# LVDS_Driver.net
KiCad netlist of a schematic drawn in Altium Designer
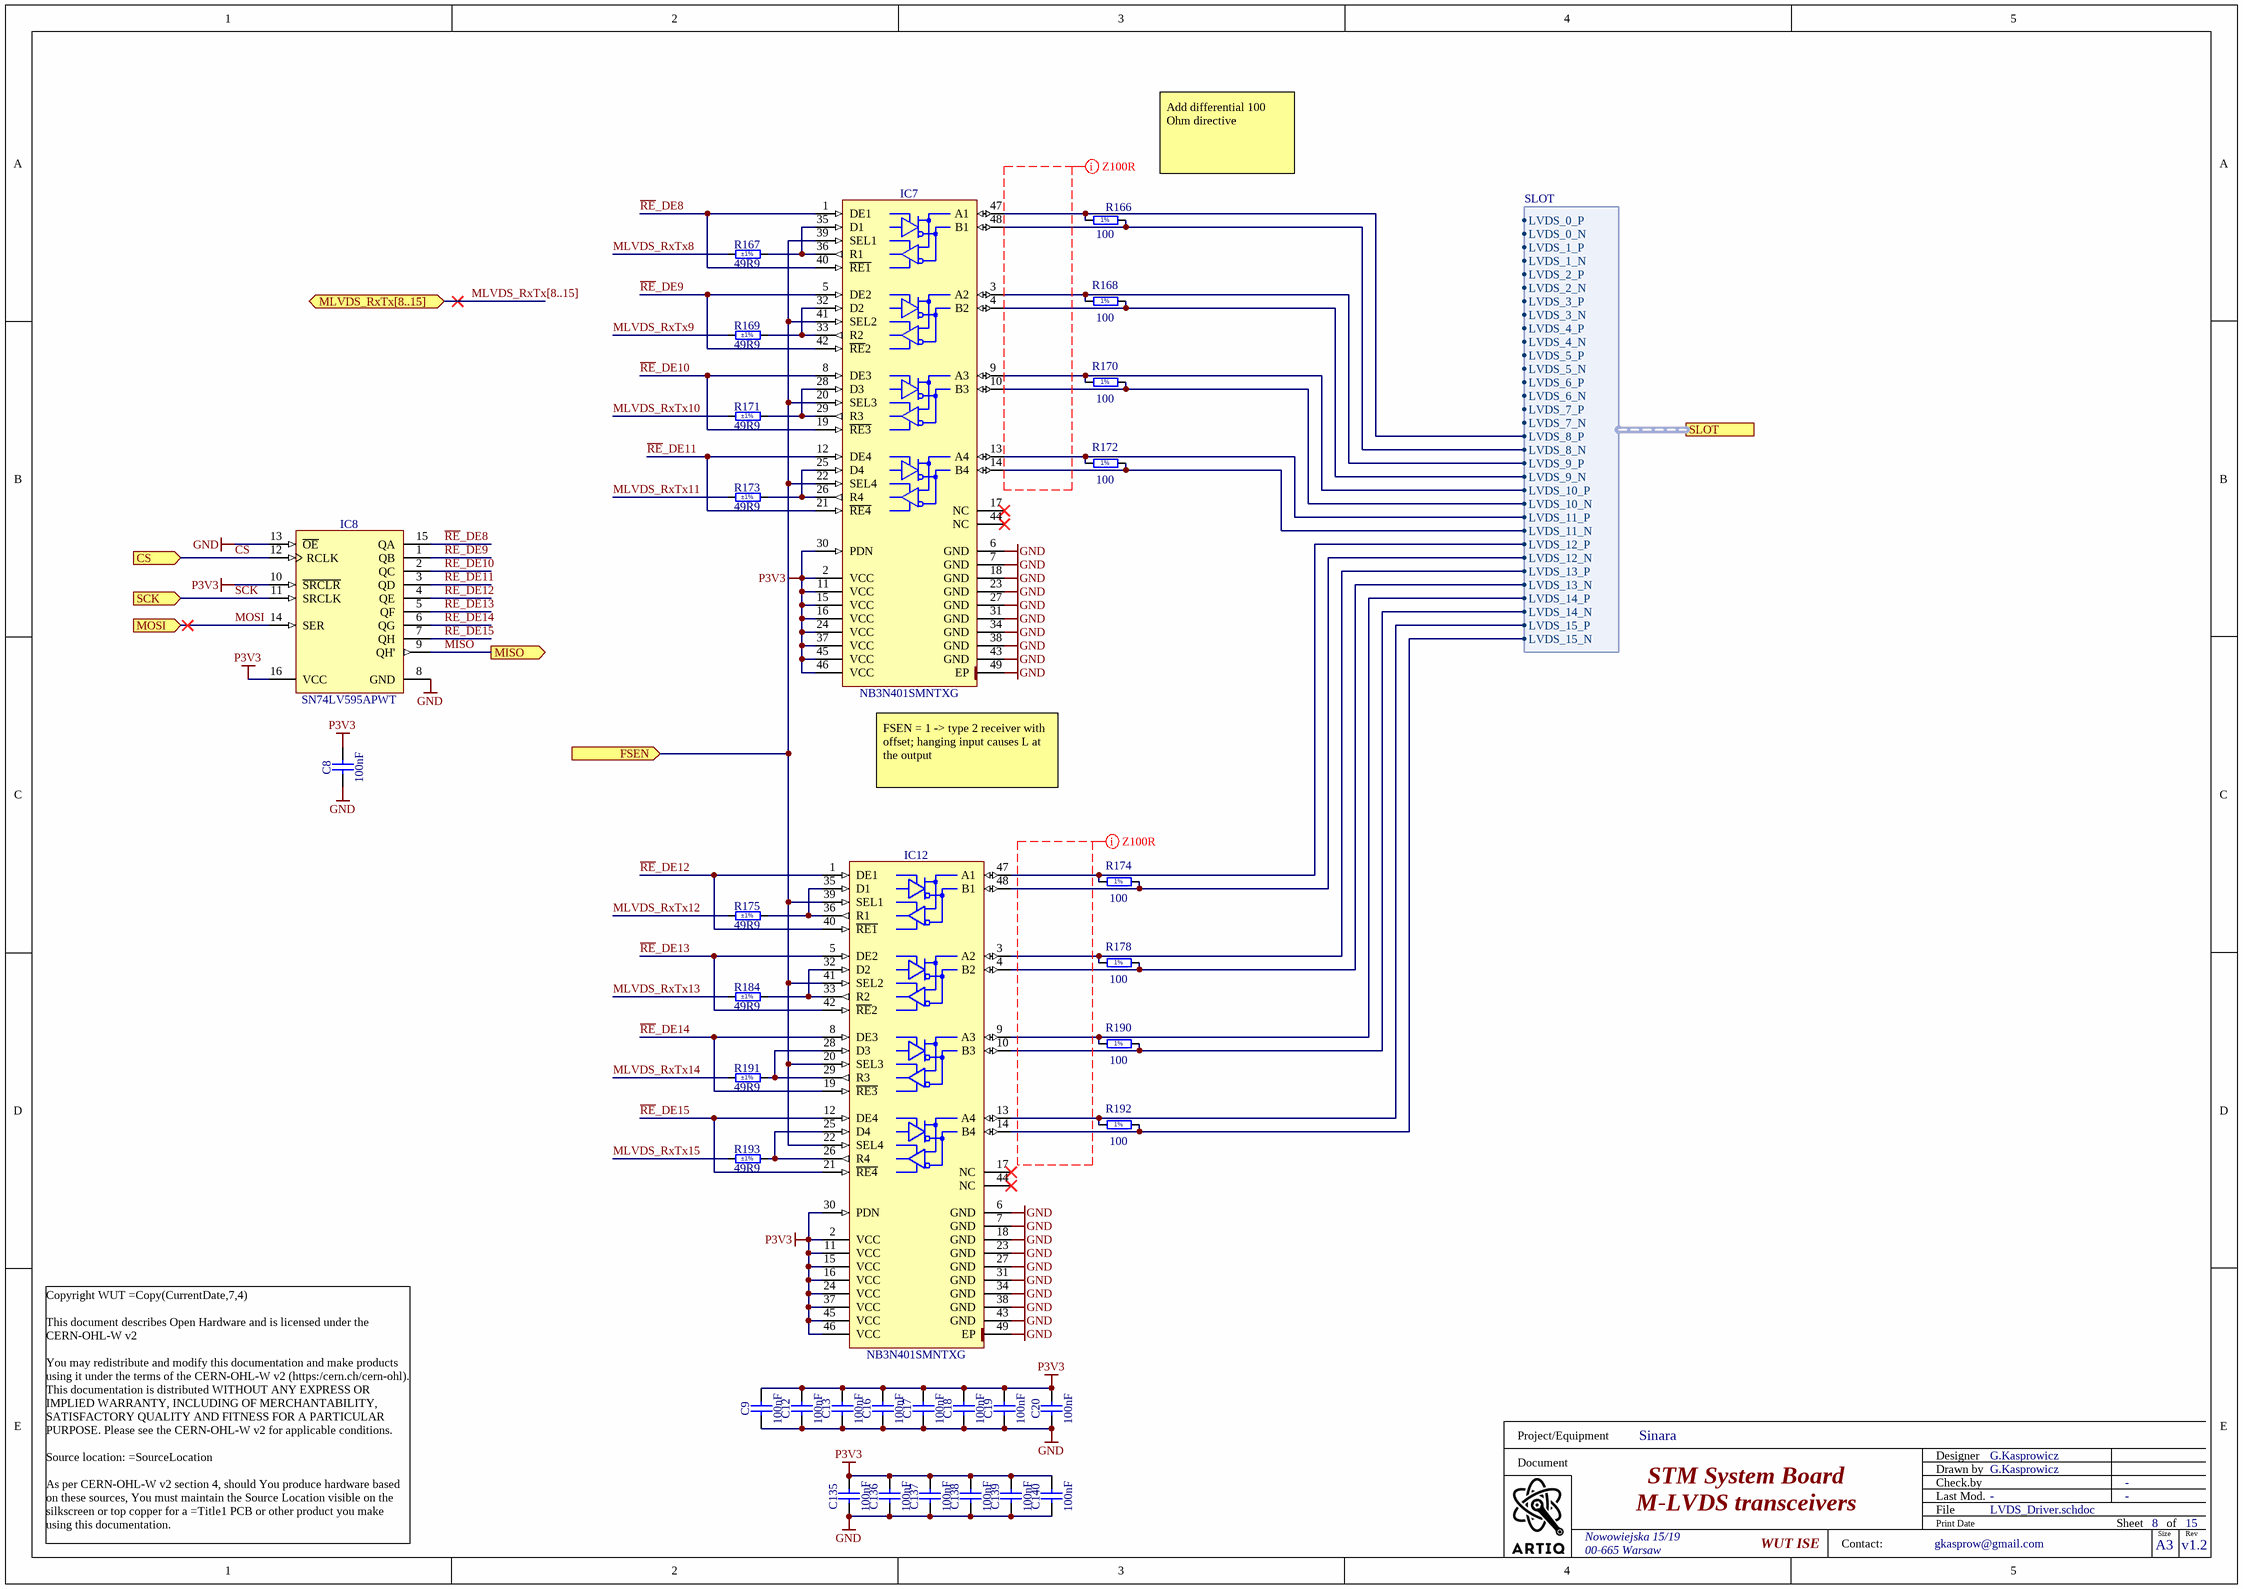
[diagram p0: LVDS_Driver.schdoc]

(export (version "E")
  (design (tool "Eeschema 10.0.6"))
  (components
    (comp (ref "C8")
      (value "100nF")
      (footprint "CAPC1005X55N")
      (description "Non-polarised capacitor")
      (fields
        (field (name "PART NUMBER") "CC0402_100NF_16V_10%_X5R")
        (field (name "VOLTAGE") "16V")
        (field (name "AUTHOR") "CERN DEM JLC")
      )
      (libsource (lib "Capacitors") (part "Capacitor - non polarized"))
    )
    (comp (ref "C9")
      (value "100nF")
      (footprint "CAPC1005X55N")
      (description "Non-polarised capacitor")
      (fields
        (field (name "PART NUMBER") "CC0402_100NF_16V_10%_X5R")
        (field (name "VOLTAGE") "16V")
        (field (name "AUTHOR") "CERN DEM JLC")
      )
      (libsource (lib "Capacitors") (part "Capacitor - non polarized"))
    )
    (comp (ref "C12")
      (value "100nF")
      (footprint "CAPC1005X55N")
      (description "Non-polarised capacitor")
      (fields
        (field (name "PART NUMBER") "CC0402_100NF_16V_10%_X5R")
        (field (name "VOLTAGE") "16V")
        (field (name "AUTHOR") "CERN DEM JLC")
      )
      (libsource (lib "Capacitors") (part "Capacitor - non polarized"))
    )
    (comp (ref "C13")
      (value "100nF")
      (footprint "CAPC1005X55N")
      (description "Non-polarised capacitor")
      (fields
        (field (name "PART NUMBER") "CC0402_100NF_16V_10%_X5R")
        (field (name "VOLTAGE") "16V")
        (field (name "AUTHOR") "CERN DEM JLC")
      )
      (libsource (lib "Capacitors") (part "Capacitor - non polarized"))
    )
    (comp (ref "C16")
      (value "100nF")
      (footprint "CAPC1005X55N")
      (description "Non-polarised capacitor")
      (fields
        (field (name "PART NUMBER") "CC0402_100NF_16V_10%_X5R")
        (field (name "VOLTAGE") "16V")
        (field (name "AUTHOR") "CERN DEM JLC")
      )
      (libsource (lib "Capacitors") (part "Capacitor - non polarized"))
    )
    (comp (ref "C17")
      (value "100nF")
      (footprint "CAPC1005X55N")
      (description "Non-polarised capacitor")
      (fields
        (field (name "PART NUMBER") "CC0402_100NF_16V_10%_X5R")
        (field (name "VOLTAGE") "16V")
        (field (name "AUTHOR") "CERN DEM JLC")
      )
      (libsource (lib "Capacitors") (part "Capacitor - non polarized"))
    )
    (comp (ref "C18")
      (value "100nF")
      (footprint "CAPC1005X55N")
      (description "Non-polarised capacitor")
      (fields
        (field (name "PART NUMBER") "CC0402_100NF_16V_10%_X5R")
        (field (name "VOLTAGE") "16V")
        (field (name "AUTHOR") "CERN DEM JLC")
      )
      (libsource (lib "Capacitors") (part "Capacitor - non polarized"))
    )
    (comp (ref "C19")
      (value "100nF")
      (footprint "CAPC1005X55N")
      (description "Non-polarised capacitor")
      (fields
        (field (name "PART NUMBER") "CC0402_100NF_16V_10%_X5R")
        (field (name "VOLTAGE") "16V")
        (field (name "AUTHOR") "CERN DEM JLC")
      )
      (libsource (lib "Capacitors") (part "Capacitor - non polarized"))
    )
    (comp (ref "C20")
      (value "100nF")
      (footprint "CAPC1005X55N")
      (description "Non-polarised capacitor")
      (fields
        (field (name "PART NUMBER") "CC0402_100NF_16V_10%_X5R")
        (field (name "VOLTAGE") "16V")
        (field (name "AUTHOR") "CERN DEM JLC")
      )
      (libsource (lib "Capacitors") (part "Capacitor - non polarized"))
    )
    (comp (ref "C135")
      (value "100nF")
      (footprint "CAPC1005X55N")
      (description "Non-polarised capacitor")
      (fields
        (field (name "PART NUMBER") "CC0402_100NF_16V_10%_X5R")
        (field (name "VOLTAGE") "16V")
        (field (name "AUTHOR") "CERN DEM JLC")
      )
      (libsource (lib "Capacitors") (part "Capacitor - non polarized"))
    )
    (comp (ref "C136")
      (value "100nF")
      (footprint "CAPC1005X55N")
      (description "Non-polarised capacitor")
      (fields
        (field (name "PART NUMBER") "CC0402_100NF_16V_10%_X5R")
        (field (name "VOLTAGE") "16V")
        (field (name "AUTHOR") "CERN DEM JLC")
      )
      (libsource (lib "Capacitors") (part "Capacitor - non polarized"))
    )
    (comp (ref "C137")
      (value "100nF")
      (footprint "CAPC1005X55N")
      (description "Non-polarised capacitor")
      (fields
        (field (name "PART NUMBER") "CC0402_100NF_16V_10%_X5R")
        (field (name "VOLTAGE") "16V")
        (field (name "AUTHOR") "CERN DEM JLC")
      )
      (libsource (lib "Capacitors") (part "Capacitor - non polarized"))
    )
    (comp (ref "C138")
      (value "100nF")
      (footprint "CAPC1005X55N")
      (description "Non-polarised capacitor")
      (fields
        (field (name "PART NUMBER") "CC0402_100NF_16V_10%_X5R")
        (field (name "VOLTAGE") "16V")
        (field (name "AUTHOR") "CERN DEM JLC")
      )
      (libsource (lib "Capacitors") (part "Capacitor - non polarized"))
    )
    (comp (ref "C139")
      (value "100nF")
      (footprint "CAPC1005X55N")
      (description "Non-polarised capacitor")
      (fields
        (field (name "PART NUMBER") "CC0402_100NF_16V_10%_X5R")
        (field (name "VOLTAGE") "16V")
        (field (name "AUTHOR") "CERN DEM JLC")
      )
      (libsource (lib "Capacitors") (part "Capacitor - non polarized"))
    )
    (comp (ref "C140")
      (value "100nF")
      (footprint "CAPC1005X55N")
      (description "Non-polarised capacitor")
      (fields
        (field (name "PART NUMBER") "CC0402_100NF_16V_10%_X5R")
        (field (name "VOLTAGE") "16V")
        (field (name "AUTHOR") "CERN DEM JLC")
      )
      (libsource (lib "Capacitors") (part "Capacitor - non polarized"))
    )
    (comp (ref "IC7")
      (value "NB3N401SMNTXG")
      (footprint "QFN50P700X700X100-49N-S420")
      (description "3.3 V Quad Channel Half‐Duplex M-LVDS Driver Receiver")
      (fields (field (name "MANUFACTURER") "ON SEMICONDUCTOR") (field (name "AUTHOR") "CERN DEM HF"))
      (libsource (lib "ICs And Semiconductors") (part "NB3N401S"))
    )
    (comp (ref "IC8")
      (value "SN74LV595APWT")
      (footprint "SOP65P640X120-16N")
      (description "8-Bit Shift Register With 3-State Output Register")
      (fields (field (name "MANUFACTURER") "TEXAS INSTRUMENTS") (field (name "AUTHOR") "CERN DEM JLC"))
      (libsource (lib "ICs And Semiconductors") (part "74595"))
    )
    (comp (ref "IC12")
      (value "NB3N401SMNTXG")
      (footprint "QFN50P700X700X100-49N-S420")
      (description "3.3 V Quad Channel Half‐Duplex M-LVDS Driver Receiver")
      (fields (field (name "MANUFACTURER") "ON SEMICONDUCTOR") (field (name "AUTHOR") "CERN DEM HF"))
      (libsource (lib "ICs And Semiconductors") (part "NB3N401S"))
    )
    (comp (ref "R166")
      (value "100")
      (footprint "RESC1005X40N")
      (description "Resistor - 1%")
      (fields
        (field (name "PART NUMBER") "R0402_100R_1%_0.1W_100PPM")
        (field (name "POWER") "0.1W")
        (field (name "AUTHOR") "CERN DEM JLC")
      )
      (libsource (lib "Resistors") (part "Resistor - 1%"))
    )
    (comp (ref "R167")
      (value "49R9")
      (footprint "RESC1005X40N")
      (description "Resistor - 1%")
      (fields
        (field (name "TOLERANCE") "±1%")
        (field (name "PART NUMBER") "R0402_49R9_1%_0.0625W_100PPM")
        (field (name "POWER") "0.0625W")
        (field (name "AUTHOR") "CERN DEM JLC")
      )
      (libsource (lib "Resistors") (part "Resistor - 1%"))
    )
    (comp (ref "R168")
      (value "100")
      (footprint "RESC1005X40N")
      (description "Resistor - 1%")
      (fields
        (field (name "PART NUMBER") "R0402_100R_1%_0.1W_100PPM")
        (field (name "POWER") "0.1W")
        (field (name "AUTHOR") "CERN DEM JLC")
      )
      (libsource (lib "Resistors") (part "Resistor - 1%"))
    )
    (comp (ref "R169")
      (value "49R9")
      (footprint "RESC1005X40N")
      (description "Resistor - 1%")
      (fields
        (field (name "TOLERANCE") "±1%")
        (field (name "PART NUMBER") "R0402_49R9_1%_0.0625W_100PPM")
        (field (name "POWER") "0.0625W")
        (field (name "AUTHOR") "CERN DEM JLC")
      )
      (libsource (lib "Resistors") (part "Resistor - 1%"))
    )
    (comp (ref "R170")
      (value "100")
      (footprint "RESC1005X40N")
      (description "Resistor - 1%")
      (fields
        (field (name "PART NUMBER") "R0402_100R_1%_0.1W_100PPM")
        (field (name "POWER") "0.1W")
        (field (name "AUTHOR") "CERN DEM JLC")
      )
      (libsource (lib "Resistors") (part "Resistor - 1%"))
    )
    (comp (ref "R171")
      (value "49R9")
      (footprint "RESC1005X40N")
      (description "Resistor - 1%")
      (fields
        (field (name "TOLERANCE") "±1%")
        (field (name "PART NUMBER") "R0402_49R9_1%_0.0625W_100PPM")
        (field (name "POWER") "0.0625W")
        (field (name "AUTHOR") "CERN DEM JLC")
      )
      (libsource (lib "Resistors") (part "Resistor - 1%"))
    )
    (comp (ref "R172")
      (value "100")
      (footprint "RESC1005X40N")
      (description "Resistor - 1%")
      (fields
        (field (name "PART NUMBER") "R0402_100R_1%_0.1W_100PPM")
        (field (name "POWER") "0.1W")
        (field (name "AUTHOR") "CERN DEM JLC")
      )
      (libsource (lib "Resistors") (part "Resistor - 1%"))
    )
    (comp (ref "R173")
      (value "49R9")
      (footprint "RESC1005X40N")
      (description "Resistor - 1%")
      (fields
        (field (name "TOLERANCE") "±1%")
        (field (name "PART NUMBER") "R0402_49R9_1%_0.0625W_100PPM")
        (field (name "POWER") "0.0625W")
        (field (name "AUTHOR") "CERN DEM JLC")
      )
      (libsource (lib "Resistors") (part "Resistor - 1%"))
    )
    (comp (ref "R174")
      (value "100")
      (footprint "RESC1005X40N")
      (description "Resistor - 1%")
      (fields
        (field (name "PART NUMBER") "R0402_100R_1%_0.1W_100PPM")
        (field (name "POWER") "0.1W")
        (field (name "AUTHOR") "CERN DEM JLC")
      )
      (libsource (lib "Resistors") (part "Resistor - 1%"))
    )
    (comp (ref "R175")
      (value "49R9")
      (footprint "RESC1005X40N")
      (description "Resistor - 1%")
      (fields
        (field (name "TOLERANCE") "±1%")
        (field (name "PART NUMBER") "R0402_49R9_1%_0.0625W_100PPM")
        (field (name "POWER") "0.0625W")
        (field (name "AUTHOR") "CERN DEM JLC")
      )
      (libsource (lib "Resistors") (part "Resistor - 1%"))
    )
    (comp (ref "R178")
      (value "100")
      (footprint "RESC1005X40N")
      (description "Resistor - 1%")
      (fields
        (field (name "PART NUMBER") "R0402_100R_1%_0.1W_100PPM")
        (field (name "POWER") "0.1W")
        (field (name "AUTHOR") "CERN DEM JLC")
      )
      (libsource (lib "Resistors") (part "Resistor - 1%"))
    )
    (comp (ref "R184")
      (value "49R9")
      (footprint "RESC1005X40N")
      (description "Resistor - 1%")
      (fields
        (field (name "TOLERANCE") "±1%")
        (field (name "PART NUMBER") "R0402_49R9_1%_0.0625W_100PPM")
        (field (name "POWER") "0.0625W")
        (field (name "AUTHOR") "CERN DEM JLC")
      )
      (libsource (lib "Resistors") (part "Resistor - 1%"))
    )
    (comp (ref "R190")
      (value "100")
      (footprint "RESC1005X40N")
      (description "Resistor - 1%")
      (fields
        (field (name "PART NUMBER") "R0402_100R_1%_0.1W_100PPM")
        (field (name "POWER") "0.1W")
        (field (name "AUTHOR") "CERN DEM JLC")
      )
      (libsource (lib "Resistors") (part "Resistor - 1%"))
    )
    (comp (ref "R191")
      (value "49R9")
      (footprint "RESC1005X40N")
      (description "Resistor - 1%")
      (fields
        (field (name "TOLERANCE") "±1%")
        (field (name "PART NUMBER") "R0402_49R9_1%_0.0625W_100PPM")
        (field (name "POWER") "0.0625W")
        (field (name "AUTHOR") "CERN DEM JLC")
      )
      (libsource (lib "Resistors") (part "Resistor - 1%"))
    )
    (comp (ref "R192")
      (value "100")
      (footprint "RESC1005X40N")
      (description "Resistor - 1%")
      (fields
        (field (name "PART NUMBER") "R0402_100R_1%_0.1W_100PPM")
        (field (name "POWER") "0.1W")
        (field (name "AUTHOR") "CERN DEM JLC")
      )
      (libsource (lib "Resistors") (part "Resistor - 1%"))
    )
    (comp (ref "R193")
      (value "49R9")
      (footprint "RESC1005X40N")
      (description "Resistor - 1%")
      (fields
        (field (name "TOLERANCE") "±1%")
        (field (name "PART NUMBER") "R0402_49R9_1%_0.0625W_100PPM")
        (field (name "POWER") "0.0625W")
        (field (name "AUTHOR") "CERN DEM JLC")
      )
      (libsource (lib "Resistors") (part "Resistor - 1%"))
    )
  )
  (nets
    (net (code "2") (name "/CS") (class "Default")
      (node (ref "IC8") (pin "12") (pinfunction "RCLK_12") (pintype "input"))
    )
    (net (code "3") (name "/FSEN") (class "Default")
      (node (ref "IC12") (pin "20") (pinfunction "SEL3_20") (pintype "input"))
      (node (ref "IC12") (pin "22") (pinfunction "SEL4_22") (pintype "input"))
      (node (ref "IC12") (pin "39") (pinfunction "SEL1_39") (pintype "input"))
      (node (ref "IC12") (pin "41") (pinfunction "SEL2_41") (pintype "input"))
      (node (ref "IC7") (pin "20") (pinfunction "SEL3_20") (pintype "input"))
      (node (ref "IC7") (pin "22") (pinfunction "SEL4_22") (pintype "input"))
      (node (ref "IC7") (pin "39") (pinfunction "SEL1_39") (pintype "input"))
      (node (ref "IC7") (pin "41") (pinfunction "SEL2_41") (pintype "input"))
    )
    (net (code "4") (name "/MISO") (class "Default")
      (node (ref "IC8") (pin "9") (pinfunction "QH'_9") (pintype "output"))
    )
    (net (code "5") (name "/MLVDS_RxTx8") (class "Default")
      (node (ref "R167") (pin "1") (pinfunction "1_1") (pintype "passive"))
    )
    (net (code "6") (name "/MLVDS_RxTx9") (class "Default")
      (node (ref "R169") (pin "1") (pinfunction "1_1") (pintype "passive"))
    )
    (net (code "7") (name "/MLVDS_RxTx10") (class "Default")
      (node (ref "R171") (pin "1") (pinfunction "1_1") (pintype "passive"))
    )
    (net (code "8") (name "/MLVDS_RxTx11") (class "Default")
      (node (ref "R173") (pin "1") (pinfunction "1_1") (pintype "passive"))
    )
    (net (code "9") (name "/MLVDS_RxTx12") (class "Default")
      (node (ref "R175") (pin "1") (pinfunction "1_1") (pintype "passive"))
    )
    (net (code "10") (name "/MLVDS_RxTx13") (class "Default")
      (node (ref "R184") (pin "1") (pinfunction "1_1") (pintype "passive"))
    )
    (net (code "11") (name "/MLVDS_RxTx14") (class "Default")
      (node (ref "R191") (pin "1") (pinfunction "1_1") (pintype "passive"))
    )
    (net (code "12") (name "/MLVDS_RxTx15") (class "Default")
      (node (ref "R193") (pin "1") (pinfunction "1_1") (pintype "passive"))
    )
    (net (code "14") (name "/MOSI") (class "Default")
      (node (ref "IC8") (pin "14") (pinfunction "SER_14") (pintype "input"))
    )
    (net (code "15") (name "/SCK") (class "Default")
      (node (ref "IC8") (pin "11") (pinfunction "SRCLK_11") (pintype "input"))
    )
    (net (code "17") (name "/~{RE}_DE8") (class "Default")
      (node (ref "IC7") (pin "1") (pinfunction "DE1_1") (pintype "input"))
      (node (ref "IC7") (pin "40") (pinfunction "~{RE1}_40") (pintype "input"))
      (node (ref "IC8") (pin "15") (pinfunction "QA_15") (pintype "tri_state"))
    )
    (net (code "18") (name "/~{RE}_DE9") (class "Default")
      (node (ref "IC7") (pin "42") (pinfunction "~{RE}2_42") (pintype "input"))
      (node (ref "IC7") (pin "5") (pinfunction "DE2_5") (pintype "input"))
      (node (ref "IC8") (pin "1") (pinfunction "QB_1") (pintype "tri_state"))
    )
    (net (code "19") (name "/~{RE}_DE10") (class "Default")
      (node (ref "IC7") (pin "19") (pinfunction "~{RE3}_19") (pintype "input"))
      (node (ref "IC7") (pin "8") (pinfunction "DE3_8") (pintype "input"))
      (node (ref "IC8") (pin "2") (pinfunction "QC_2") (pintype "tri_state"))
    )
    (net (code "20") (name "/~{RE}_DE11") (class "Default")
      (node (ref "IC7") (pin "12") (pinfunction "DE4_12") (pintype "input"))
      (node (ref "IC7") (pin "21") (pinfunction "~{RE4}_21") (pintype "input"))
      (node (ref "IC8") (pin "3") (pinfunction "QD_3") (pintype "tri_state"))
    )
    (net (code "21") (name "/~{RE}_DE12") (class "Default")
      (node (ref "IC12") (pin "1") (pinfunction "DE1_1") (pintype "input"))
      (node (ref "IC12") (pin "40") (pinfunction "~{RE1}_40") (pintype "input"))
      (node (ref "IC8") (pin "4") (pinfunction "QE_4") (pintype "tri_state"))
    )
    (net (code "22") (name "/~{RE}_DE13") (class "Default")
      (node (ref "IC12") (pin "42") (pinfunction "~{RE}2_42") (pintype "input"))
      (node (ref "IC12") (pin "5") (pinfunction "DE2_5") (pintype "input"))
      (node (ref "IC8") (pin "5") (pinfunction "QF_5") (pintype "tri_state"))
    )
    (net (code "23") (name "/~{RE}_DE14") (class "Default")
      (node (ref "IC12") (pin "19") (pinfunction "~{RE3}_19") (pintype "input"))
      (node (ref "IC12") (pin "8") (pinfunction "DE3_8") (pintype "input"))
      (node (ref "IC8") (pin "6") (pinfunction "QG_6") (pintype "tri_state"))
    )
    (net (code "24") (name "/~{RE}_DE15") (class "Default")
      (node (ref "IC12") (pin "12") (pinfunction "DE4_12") (pintype "input"))
      (node (ref "IC12") (pin "21") (pinfunction "~{RE4}_21") (pintype "input"))
      (node (ref "IC8") (pin "7") (pinfunction "QH_7") (pintype "tri_state"))
    )
    (net (code "25") (name "GND") (class "Default")
      (node (ref "C12") (pin "1") (pinfunction "1_1") (pintype "passive"))
      (node (ref "C13") (pin "1") (pinfunction "1_1") (pintype "passive"))
      (node (ref "C135") (pin "1") (pinfunction "1_1") (pintype "passive"))
      (node (ref "C136") (pin "1") (pinfunction "1_1") (pintype "passive"))
      (node (ref "C137") (pin "1") (pinfunction "1_1") (pintype "passive"))
      (node (ref "C138") (pin "1") (pinfunction "1_1") (pintype "passive"))
      (node (ref "C139") (pin "1") (pinfunction "1_1") (pintype "passive"))
      (node (ref "C140") (pin "1") (pinfunction "1_1") (pintype "passive"))
      (node (ref "C16") (pin "1") (pinfunction "1_1") (pintype "passive"))
      (node (ref "C17") (pin "1") (pinfunction "1_1") (pintype "passive"))
      (node (ref "C18") (pin "1") (pinfunction "1_1") (pintype "passive"))
      (node (ref "C19") (pin "1") (pinfunction "1_1") (pintype "passive"))
      (node (ref "C20") (pin "1") (pinfunction "1_1") (pintype "passive"))
      (node (ref "C8") (pin "1") (pinfunction "1_1") (pintype "passive"))
      (node (ref "C9") (pin "1") (pinfunction "1_1") (pintype "passive"))
      (node (ref "IC12") (pin "18") (pinfunction "GND_18") (pintype "power_in"))
      (node (ref "IC12") (pin "23") (pinfunction "GND_23") (pintype "power_in"))
      (node (ref "IC12") (pin "27") (pinfunction "GND_27") (pintype "power_in"))
      (node (ref "IC12") (pin "31") (pinfunction "GND_31") (pintype "power_in"))
      (node (ref "IC12") (pin "34") (pinfunction "GND_34") (pintype "power_in"))
      (node (ref "IC12") (pin "38") (pinfunction "GND_38") (pintype "power_in"))
      (node (ref "IC12") (pin "43") (pinfunction "GND_43") (pintype "power_in"))
      (node (ref "IC12") (pin "49") (pinfunction "EP_49") (pintype "power_in"))
      (node (ref "IC12") (pin "6") (pinfunction "GND_6") (pintype "power_in"))
      (node (ref "IC12") (pin "7") (pinfunction "GND_7") (pintype "power_in"))
      (node (ref "IC7") (pin "18") (pinfunction "GND_18") (pintype "power_in"))
      (node (ref "IC7") (pin "23") (pinfunction "GND_23") (pintype "power_in"))
      (node (ref "IC7") (pin "27") (pinfunction "GND_27") (pintype "power_in"))
      (node (ref "IC7") (pin "31") (pinfunction "GND_31") (pintype "power_in"))
      (node (ref "IC7") (pin "34") (pinfunction "GND_34") (pintype "power_in"))
      (node (ref "IC7") (pin "38") (pinfunction "GND_38") (pintype "power_in"))
      (node (ref "IC7") (pin "43") (pinfunction "GND_43") (pintype "power_in"))
      (node (ref "IC7") (pin "49") (pinfunction "EP_49") (pintype "power_in"))
      (node (ref "IC7") (pin "6") (pinfunction "GND_6") (pintype "power_in"))
      (node (ref "IC7") (pin "7") (pinfunction "GND_7") (pintype "power_in"))
      (node (ref "IC8") (pin "13") (pinfunction "~{OE}_13") (pintype "input"))
      (node (ref "IC8") (pin "8") (pinfunction "GND_8") (pintype "power_in"))
    )
    (net (code "26") (name "Net-(IC7-A1)") (class "Default")
      (node (ref "IC7") (pin "47") (pinfunction "A1_47") (pintype "bidirectional"))
      (node (ref "R166") (pin "1") (pinfunction "1_1") (pintype "passive"))
    )
    (net (code "27") (name "Net-(IC7-A2)") (class "Default")
      (node (ref "IC7") (pin "3") (pinfunction "A2_3") (pintype "bidirectional"))
      (node (ref "R168") (pin "1") (pinfunction "1_1") (pintype "passive"))
    )
    (net (code "28") (name "Net-(IC7-A3)") (class "Default")
      (node (ref "IC7") (pin "9") (pinfunction "A3_9") (pintype "bidirectional"))
      (node (ref "R170") (pin "1") (pinfunction "1_1") (pintype "passive"))
    )
    (net (code "29") (name "Net-(IC7-A4)") (class "Default")
      (node (ref "IC7") (pin "13") (pinfunction "A4_13") (pintype "bidirectional"))
      (node (ref "R172") (pin "1") (pinfunction "1_1") (pintype "passive"))
    )
    (net (code "30") (name "Net-(IC7-B1)") (class "Default")
      (node (ref "IC7") (pin "48") (pinfunction "B1_48") (pintype "bidirectional"))
      (node (ref "R166") (pin "2") (pinfunction "2_2") (pintype "passive"))
    )
    (net (code "31") (name "Net-(IC7-B2)") (class "Default")
      (node (ref "IC7") (pin "4") (pinfunction "B2_4") (pintype "bidirectional"))
      (node (ref "R168") (pin "2") (pinfunction "2_2") (pintype "passive"))
    )
    (net (code "32") (name "Net-(IC7-B3)") (class "Default")
      (node (ref "IC7") (pin "10") (pinfunction "B3_10") (pintype "bidirectional"))
      (node (ref "R170") (pin "2") (pinfunction "2_2") (pintype "passive"))
    )
    (net (code "33") (name "Net-(IC7-B4)") (class "Default")
      (node (ref "IC7") (pin "14") (pinfunction "B4_14") (pintype "bidirectional"))
      (node (ref "R172") (pin "2") (pinfunction "2_2") (pintype "passive"))
    )
    (net (code "34") (name "Net-(IC7-D1)") (class "Default")
      (node (ref "IC7") (pin "35") (pinfunction "D1_35") (pintype "input"))
      (node (ref "IC7") (pin "36") (pinfunction "R1_36") (pintype "output"))
      (node (ref "R167") (pin "2") (pinfunction "2_2") (pintype "passive"))
    )
    (net (code "35") (name "Net-(IC7-D2)") (class "Default")
      (node (ref "IC7") (pin "32") (pinfunction "D2_32") (pintype "input"))
      (node (ref "IC7") (pin "33") (pinfunction "R2_33") (pintype "output"))
      (node (ref "R169") (pin "2") (pinfunction "2_2") (pintype "passive"))
    )
    (net (code "36") (name "Net-(IC7-D3)") (class "Default")
      (node (ref "IC7") (pin "28") (pinfunction "D3_28") (pintype "input"))
      (node (ref "IC7") (pin "29") (pinfunction "R3_29") (pintype "output"))
      (node (ref "R171") (pin "2") (pinfunction "2_2") (pintype "passive"))
    )
    (net (code "37") (name "Net-(IC7-D4)") (class "Default")
      (node (ref "IC7") (pin "25") (pinfunction "D4_25") (pintype "input"))
      (node (ref "IC7") (pin "26") (pinfunction "R4_26") (pintype "output"))
      (node (ref "R173") (pin "2") (pinfunction "2_2") (pintype "passive"))
    )
    (net (code "38") (name "Net-(IC12-A1)") (class "Default")
      (node (ref "IC12") (pin "47") (pinfunction "A1_47") (pintype "bidirectional"))
      (node (ref "R174") (pin "1") (pinfunction "1_1") (pintype "passive"))
    )
    (net (code "39") (name "Net-(IC12-A2)") (class "Default")
      (node (ref "IC12") (pin "3") (pinfunction "A2_3") (pintype "bidirectional"))
      (node (ref "R178") (pin "1") (pinfunction "1_1") (pintype "passive"))
    )
    (net (code "40") (name "Net-(IC12-A3)") (class "Default")
      (node (ref "IC12") (pin "9") (pinfunction "A3_9") (pintype "bidirectional"))
      (node (ref "R190") (pin "1") (pinfunction "1_1") (pintype "passive"))
    )
    (net (code "41") (name "Net-(IC12-A4)") (class "Default")
      (node (ref "IC12") (pin "13") (pinfunction "A4_13") (pintype "bidirectional"))
      (node (ref "R192") (pin "1") (pinfunction "1_1") (pintype "passive"))
    )
    (net (code "42") (name "Net-(IC12-B1)") (class "Default")
      (node (ref "IC12") (pin "48") (pinfunction "B1_48") (pintype "bidirectional"))
      (node (ref "R174") (pin "2") (pinfunction "2_2") (pintype "passive"))
    )
    (net (code "43") (name "Net-(IC12-B2)") (class "Default")
      (node (ref "IC12") (pin "4") (pinfunction "B2_4") (pintype "bidirectional"))
      (node (ref "R178") (pin "2") (pinfunction "2_2") (pintype "passive"))
    )
    (net (code "44") (name "Net-(IC12-B3)") (class "Default")
      (node (ref "IC12") (pin "10") (pinfunction "B3_10") (pintype "bidirectional"))
      (node (ref "R190") (pin "2") (pinfunction "2_2") (pintype "passive"))
    )
    (net (code "45") (name "Net-(IC12-B4)") (class "Default")
      (node (ref "IC12") (pin "14") (pinfunction "B4_14") (pintype "bidirectional"))
      (node (ref "R192") (pin "2") (pinfunction "2_2") (pintype "passive"))
    )
    (net (code "46") (name "Net-(IC12-D1)") (class "Default")
      (node (ref "IC12") (pin "35") (pinfunction "D1_35") (pintype "input"))
      (node (ref "IC12") (pin "36") (pinfunction "R1_36") (pintype "output"))
      (node (ref "R175") (pin "2") (pinfunction "2_2") (pintype "passive"))
    )
    (net (code "47") (name "Net-(IC12-D2)") (class "Default")
      (node (ref "IC12") (pin "32") (pinfunction "D2_32") (pintype "input"))
      (node (ref "IC12") (pin "33") (pinfunction "R2_33") (pintype "output"))
      (node (ref "R184") (pin "2") (pinfunction "2_2") (pintype "passive"))
    )
    (net (code "48") (name "Net-(IC12-D3)") (class "Default")
      (node (ref "IC12") (pin "28") (pinfunction "D3_28") (pintype "input"))
      (node (ref "IC12") (pin "29") (pinfunction "R3_29") (pintype "output"))
      (node (ref "R191") (pin "2") (pinfunction "2_2") (pintype "passive"))
    )
    (net (code "49") (name "Net-(IC12-D4)") (class "Default")
      (node (ref "IC12") (pin "25") (pinfunction "D4_25") (pintype "input"))
      (node (ref "IC12") (pin "26") (pinfunction "R4_26") (pintype "output"))
      (node (ref "R193") (pin "2") (pinfunction "2_2") (pintype "passive"))
    )
    (net (code "50") (name "P3V3") (class "Default")
      (node (ref "C12") (pin "2") (pinfunction "2_2") (pintype "passive"))
      (node (ref "C13") (pin "2") (pinfunction "2_2") (pintype "passive"))
      (node (ref "C135") (pin "2") (pinfunction "2_2") (pintype "passive"))
      (node (ref "C136") (pin "2") (pinfunction "2_2") (pintype "passive"))
      (node (ref "C137") (pin "2") (pinfunction "2_2") (pintype "passive"))
      (node (ref "C138") (pin "2") (pinfunction "2_2") (pintype "passive"))
      (node (ref "C139") (pin "2") (pinfunction "2_2") (pintype "passive"))
      (node (ref "C140") (pin "2") (pinfunction "2_2") (pintype "passive"))
      (node (ref "C16") (pin "2") (pinfunction "2_2") (pintype "passive"))
      (node (ref "C17") (pin "2") (pinfunction "2_2") (pintype "passive"))
      (node (ref "C18") (pin "2") (pinfunction "2_2") (pintype "passive"))
      (node (ref "C19") (pin "2") (pinfunction "2_2") (pintype "passive"))
      (node (ref "C20") (pin "2") (pinfunction "2_2") (pintype "passive"))
      (node (ref "C8") (pin "2") (pinfunction "2_2") (pintype "passive"))
      (node (ref "C9") (pin "2") (pinfunction "2_2") (pintype "passive"))
      (node (ref "IC12") (pin "11") (pinfunction "VCC_11") (pintype "power_in"))
      (node (ref "IC12") (pin "15") (pinfunction "VCC_15") (pintype "power_in"))
      (node (ref "IC12") (pin "16") (pinfunction "VCC_16") (pintype "power_in"))
      (node (ref "IC12") (pin "2") (pinfunction "VCC_2") (pintype "power_in"))
      (node (ref "IC12") (pin "24") (pinfunction "VCC_24") (pintype "power_in"))
      (node (ref "IC12") (pin "30") (pinfunction "PDN_30") (pintype "input"))
      (node (ref "IC12") (pin "37") (pinfunction "VCC_37") (pintype "power_in"))
      (node (ref "IC12") (pin "45") (pinfunction "VCC_45") (pintype "power_in"))
      (node (ref "IC12") (pin "46") (pinfunction "VCC_46") (pintype "power_in"))
      (node (ref "IC7") (pin "11") (pinfunction "VCC_11") (pintype "power_in"))
      (node (ref "IC7") (pin "15") (pinfunction "VCC_15") (pintype "power_in"))
      (node (ref "IC7") (pin "16") (pinfunction "VCC_16") (pintype "power_in"))
      (node (ref "IC7") (pin "2") (pinfunction "VCC_2") (pintype "power_in"))
      (node (ref "IC7") (pin "24") (pinfunction "VCC_24") (pintype "power_in"))
      (node (ref "IC7") (pin "30") (pinfunction "PDN_30") (pintype "input"))
      (node (ref "IC7") (pin "37") (pinfunction "VCC_37") (pintype "power_in"))
      (node (ref "IC7") (pin "45") (pinfunction "VCC_45") (pintype "power_in"))
      (node (ref "IC7") (pin "46") (pinfunction "VCC_46") (pintype "power_in"))
      (node (ref "IC8") (pin "10") (pinfunction "~{SRCLR}_10") (pintype "input"))
      (node (ref "IC8") (pin "16") (pinfunction "VCC_16") (pintype "power_in"))
    )
    (net (code "51") (name "unconnected-(IC7-NC-Pad17)") (class "Default")
      (node (ref "IC7") (pin "17") (pinfunction "NC_17") (pintype "passive+no_connect"))
    )
    (net (code "52") (name "unconnected-(IC7-NC-Pad44)") (class "Default")
      (node (ref "IC7") (pin "44") (pinfunction "NC_44") (pintype "passive+no_connect"))
    )
    (net (code "53") (name "unconnected-(IC12-NC-Pad17)") (class "Default")
      (node (ref "IC12") (pin "17") (pinfunction "NC_17") (pintype "passive+no_connect"))
    )
    (net (code "54") (name "unconnected-(IC12-NC-Pad44)") (class "Default")
      (node (ref "IC12") (pin "44") (pinfunction "NC_44") (pintype "passive+no_connect"))
    )
  )
)
